# 2228_Recepteur_Alimentation.net
KiCad netlist of a schematic drawn in Altium Designer
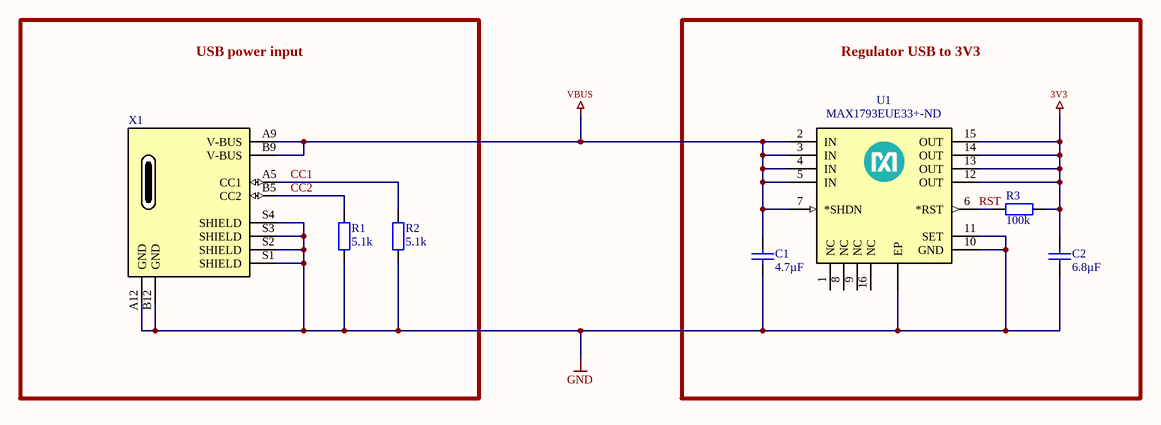
[diagram p0: 2228_Recepteur_Alimentation.SchDoc]

(export (version "E")
  (design (tool "Eeschema 10.0.6"))
  (components
    (comp (ref "C1")
      (value "4.7µF")
      (footprint "CAP_0805")
      (description "Ceramic capacitor")
      (fields (field (name "Comment") "CAP_SMD"))
      (libsource (lib "2228_AlarmeFenetre_Symbols") (part "CAP_SMD"))
    )
    (comp (ref "C2")
      (value "6.8µF")
      (footprint "CAP_0805")
      (description "Ceramic capacitor")
      (fields (field (name "Comment") "CAP_SMD"))
      (libsource (lib "2228_AlarmeFenetre_Symbols") (part "CAP_SMD"))
    )
    (comp (ref "R1")
      (value "5.1k")
      (footprint "RES_0805")
      (fields (field (name "Comment") "RES_SMD"))
      (libsource (lib "2228_AlarmeFenetre_Symbols") (part "RES_SMD"))
    )
    (comp (ref "R2")
      (value "5.1k")
      (footprint "RES_0805")
      (fields (field (name "Comment") "RES_SMD"))
      (libsource (lib "2228_AlarmeFenetre_Symbols") (part "RES_SMD"))
    )
    (comp (ref "R3")
      (value "100k")
      (footprint "RES_0805")
      (fields (field (name "Comment") "RES_SMD"))
      (libsource (lib "") (part "RES_SMD_1"))
    )
    (comp (ref "U1")
      (value "MAX1793EUE33+")
      (footprint "2228_AlarmeFenetre_Footprints:SOP65P638X110-17N")
      (fields (field (name "SUPPLIER PART NUMBER 1") "MAX1793EUE33+-ND"))
      (libsource (lib "2228_AlarmeFenetre_Symbols") (part "MAX1793"))
    )
    (comp (ref "X1")
      (value "UJC-HP-3-SMT-TR")
      (footprint "2228_AlarmeFenetre_Footprints:CUI_UJC-HP-3-SMT-TR")
      (description "Type C, 3 A, Right Angle, Surface Mount (SMT), Power-Only USB Receptacle")
      (fields (field (name "MANUFACTURER") "CUI Devices"))
      (libsource (lib "2228_AlarmeFenetre_Symbols") (part "USB-C_CUI"))
    )
  )
  (nets
    (net (code "1") (name "/CC1") (class "Default")
      (node (ref "R2") (pin "2") (pinfunction "2_2") (pintype "passive"))
      (node (ref "X1") (pin "A5") (pinfunction "CC1_A5") (pintype "bidirectional"))
    )
    (net (code "2") (name "/CC2") (class "Default")
      (node (ref "R1") (pin "2") (pinfunction "2_2") (pintype "passive"))
      (node (ref "X1") (pin "B5") (pinfunction "CC2_B5") (pintype "bidirectional"))
    )
    (net (code "3") (name "/RST") (class "Default")
      (node (ref "R3") (pin "1") (pinfunction "1_1") (pintype "passive"))
      (node (ref "U1") (pin "6") (pinfunction "*RST_6") (pintype "output"))
    )
    (net (code "4") (name "3V3") (class "Default")
      (node (ref "C2") (pin "2") (pinfunction "2_2") (pintype "passive"))
      (node (ref "R3") (pin "2") (pinfunction "2_2") (pintype "passive"))
      (node (ref "U1") (pin "12") (pinfunction "OUT_12") (pintype "power_in"))
      (node (ref "U1") (pin "13") (pinfunction "OUT_13") (pintype "power_in"))
      (node (ref "U1") (pin "14") (pinfunction "OUT_14") (pintype "power_in"))
      (node (ref "U1") (pin "15") (pinfunction "OUT_15") (pintype "power_in"))
    )
    (net (code "5") (name "GND") (class "Default")
      (node (ref "C1") (pin "1") (pinfunction "1_1") (pintype "passive"))
      (node (ref "C2") (pin "1") (pinfunction "1_1") (pintype "passive"))
      (node (ref "R1") (pin "1") (pinfunction "1_1") (pintype "passive"))
      (node (ref "R2") (pin "1") (pinfunction "1_1") (pintype "passive"))
      (node (ref "U1") (pin "0") (pinfunction "EP_0") (pintype "passive"))
      (node (ref "U1") (pin "10") (pinfunction "GND_10") (pintype "power_in"))
      (node (ref "U1") (pin "11") (pinfunction "SET_11") (pintype "power_in"))
      (node (ref "X1") (pin "A12") (pinfunction "GND_A12") (pintype "power_in"))
      (node (ref "X1") (pin "B12") (pinfunction "GND_B12") (pintype "power_in"))
      (node (ref "X1") (pin "S1") (pinfunction "SHIELD_S1") (pintype "passive"))
      (node (ref "X1") (pin "S2") (pinfunction "SHIELD_S2") (pintype "passive"))
      (node (ref "X1") (pin "S3") (pinfunction "SHIELD_S3") (pintype "passive"))
      (node (ref "X1") (pin "S4") (pinfunction "SHIELD_S4") (pintype "passive"))
    )
    (net (code "6") (name "VBUS") (class "Default")
      (node (ref "C1") (pin "2") (pinfunction "2_2") (pintype "passive"))
      (node (ref "U1") (pin "2") (pinfunction "IN_2") (pintype "power_in"))
      (node (ref "U1") (pin "3") (pinfunction "IN_3") (pintype "power_in"))
      (node (ref "U1") (pin "4") (pinfunction "IN_4") (pintype "power_in"))
      (node (ref "U1") (pin "5") (pinfunction "IN_5") (pintype "power_in"))
      (node (ref "U1") (pin "7") (pinfunction "*SHDN_7") (pintype "input"))
      (node (ref "X1") (pin "A9") (pinfunction "V-BUS_A9") (pintype "power_in"))
      (node (ref "X1") (pin "B9") (pinfunction "V-BUS_B9") (pintype "power_in"))
    )
    (net (code "7") (name "unconnected-(U1-NC-Pad1)") (class "Default")
      (node (ref "U1") (pin "1") (pinfunction "NC_1") (pintype "passive"))
    )
    (net (code "8") (name "unconnected-(U1-NC-Pad8)") (class "Default")
      (node (ref "U1") (pin "8") (pinfunction "NC_8") (pintype "passive"))
    )
    (net (code "9") (name "unconnected-(U1-NC-Pad9)") (class "Default")
      (node (ref "U1") (pin "9") (pinfunction "NC_9") (pintype "passive"))
    )
    (net (code "10") (name "unconnected-(U1-NC-Pad16)") (class "Default")
      (node (ref "U1") (pin "16") (pinfunction "NC_16") (pintype "passive"))
    )
  )
)
